# Schematic_Seatalk_to_TTL_2021-10-25.net
KiCad netlist of a schematic drawn in EasyEDA
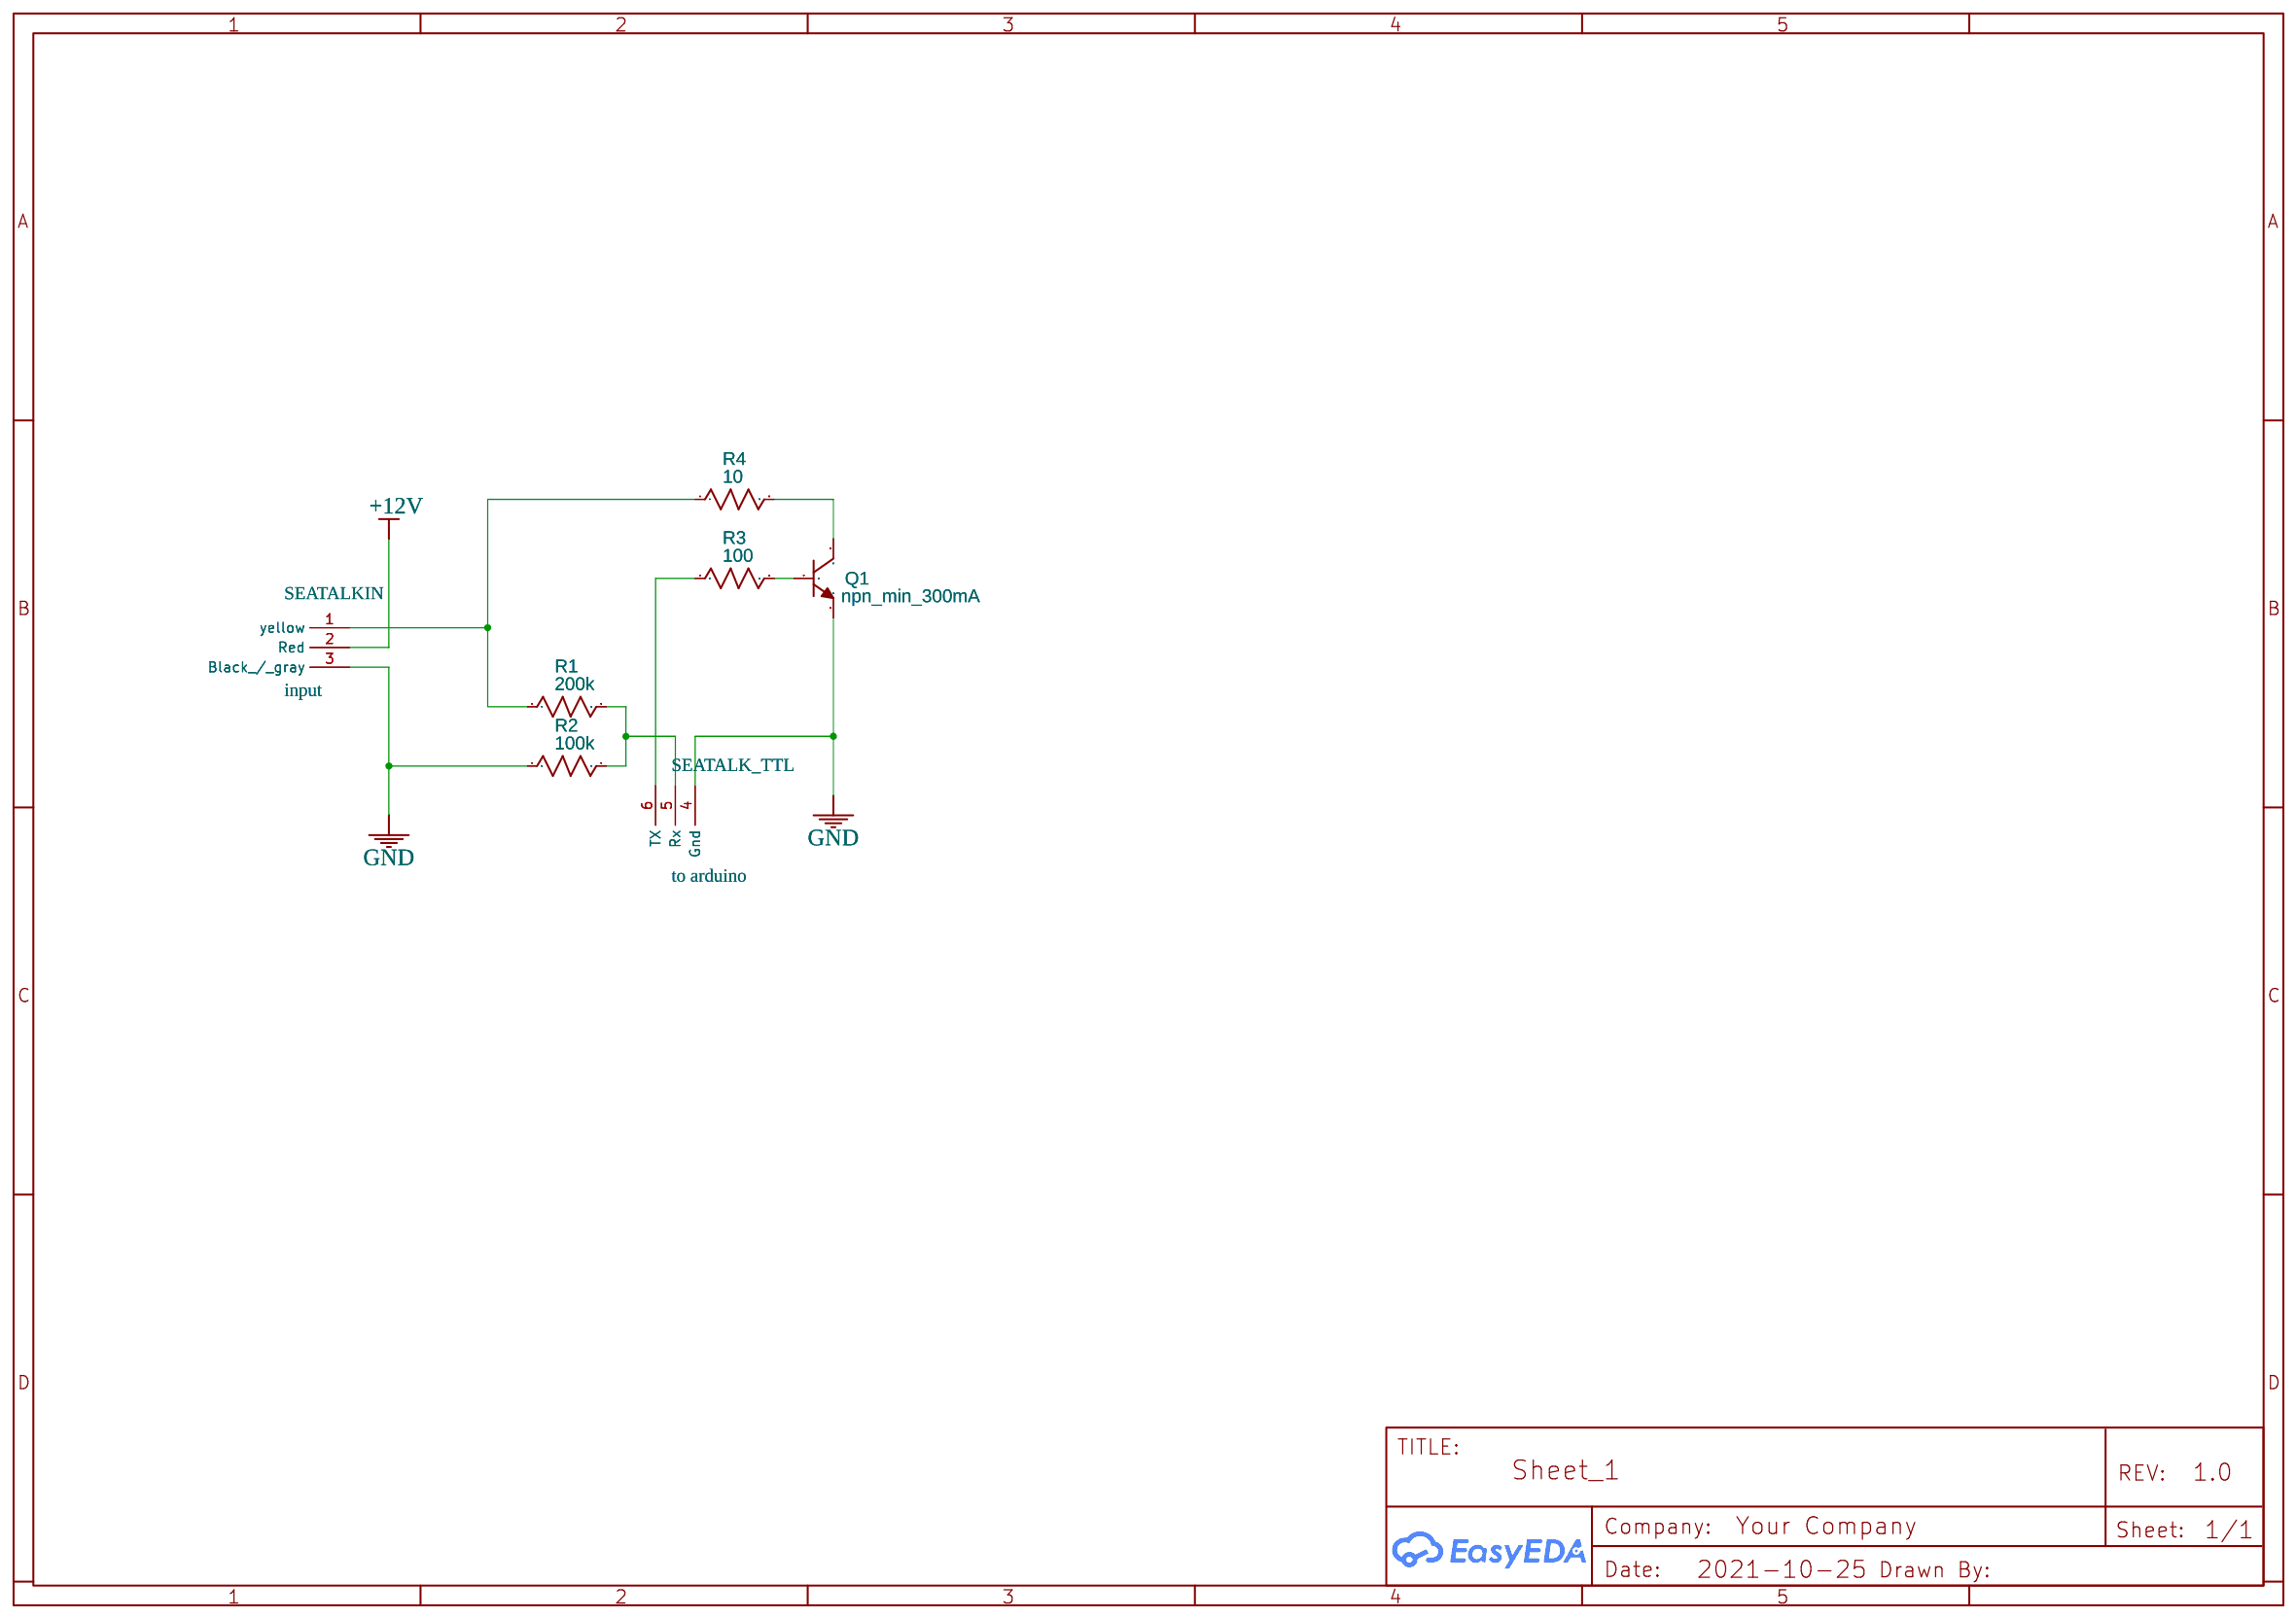
[diagram p0: schematic sheet]

(export (version "E")
  (design (tool "Eeschema 10.0.6"))
  (components
    (comp (ref "Q1")
      (value "npn_min_300mA")
      (fields
        (field (name "BOM_Manufacturer Part") "2n3904S-RTK/PS")
        (field (name "BOM_Supplier Part") "C18536")
      )
      (libsource (lib "") (part "2N3904(SOT-23)"))
    )
    (comp (ref "R1") (value "200k") (libsource (lib "") (part "R_0603_US")))
    (comp (ref "R2") (value "100k") (libsource (lib "") (part "R_0603_US")))
    (comp (ref "R3") (value "100") (libsource (lib "") (part "R_0603_US")))
    (comp (ref "R4") (value "10") (libsource (lib "") (part "R_0603_US")))
    (comp (ref "SEATALKIN") (value "input") (libsource (lib "") (part "Unknown_135_-485")))
    (comp (ref "SEATALK_TTL") (value "to arduino") (libsource (lib "") (part "Unknown_335_-395")))
  )
  (nets
    (net (code "1") (name "+12V") (class "Default")
      (node (ref "SEATALKIN") (pin "2") (pinfunction "Red_2") (pintype "unspecified"))
    )
    (net (code "2") (name "GND") (class "Default")
      (node (ref "Q1") (pin "1") (pinfunction "E_1") (pintype "input"))
      (node (ref "R2") (pin "1") (pinfunction "1_1") (pintype "unspecified"))
      (node (ref "SEATALKIN") (pin "3") (pinfunction "Black_/_gray_3") (pintype "unspecified"))
      (node (ref "SEATALK_TTL") (pin "4") (pinfunction "Gnd_4") (pintype "unspecified"))
    )
    (net (code "3") (name "Net-(Q1-B)") (class "Default")
      (node (ref "Q1") (pin "2") (pinfunction "B_2") (pintype "input"))
      (node (ref "R3") (pin "2") (pinfunction "2_2") (pintype "unspecified"))
    )
    (net (code "4") (name "Net-(Q1-C)") (class "Default")
      (node (ref "Q1") (pin "3") (pinfunction "C_3") (pintype "input"))
      (node (ref "R4") (pin "2") (pinfunction "2_2") (pintype "unspecified"))
    )
    (net (code "5") (name "Net-(SEATALKIN-yellow)") (class "Default")
      (node (ref "R1") (pin "1") (pinfunction "1_1") (pintype "unspecified"))
      (node (ref "R4") (pin "1") (pinfunction "1_1") (pintype "unspecified"))
      (node (ref "SEATALKIN") (pin "1") (pinfunction "yellow_1") (pintype "unspecified"))
    )
    (net (code "6") (name "Net-(SEATALK_TTL-Rx)") (class "Default")
      (node (ref "R1") (pin "2") (pinfunction "2_2") (pintype "unspecified"))
      (node (ref "R2") (pin "2") (pinfunction "2_2") (pintype "unspecified"))
      (node (ref "SEATALK_TTL") (pin "5") (pinfunction "Rx_5") (pintype "unspecified"))
    )
    (net (code "7") (name "Net-(SEATALK_TTL-TX)") (class "Default")
      (node (ref "R3") (pin "1") (pinfunction "1_1") (pintype "unspecified"))
      (node (ref "SEATALK_TTL") (pin "6") (pinfunction "TX_6") (pintype "unspecified"))
    )
  )
)
